# 7seg_interface_unit.net
KiCad netlist of a schematic drawn in EAGLE
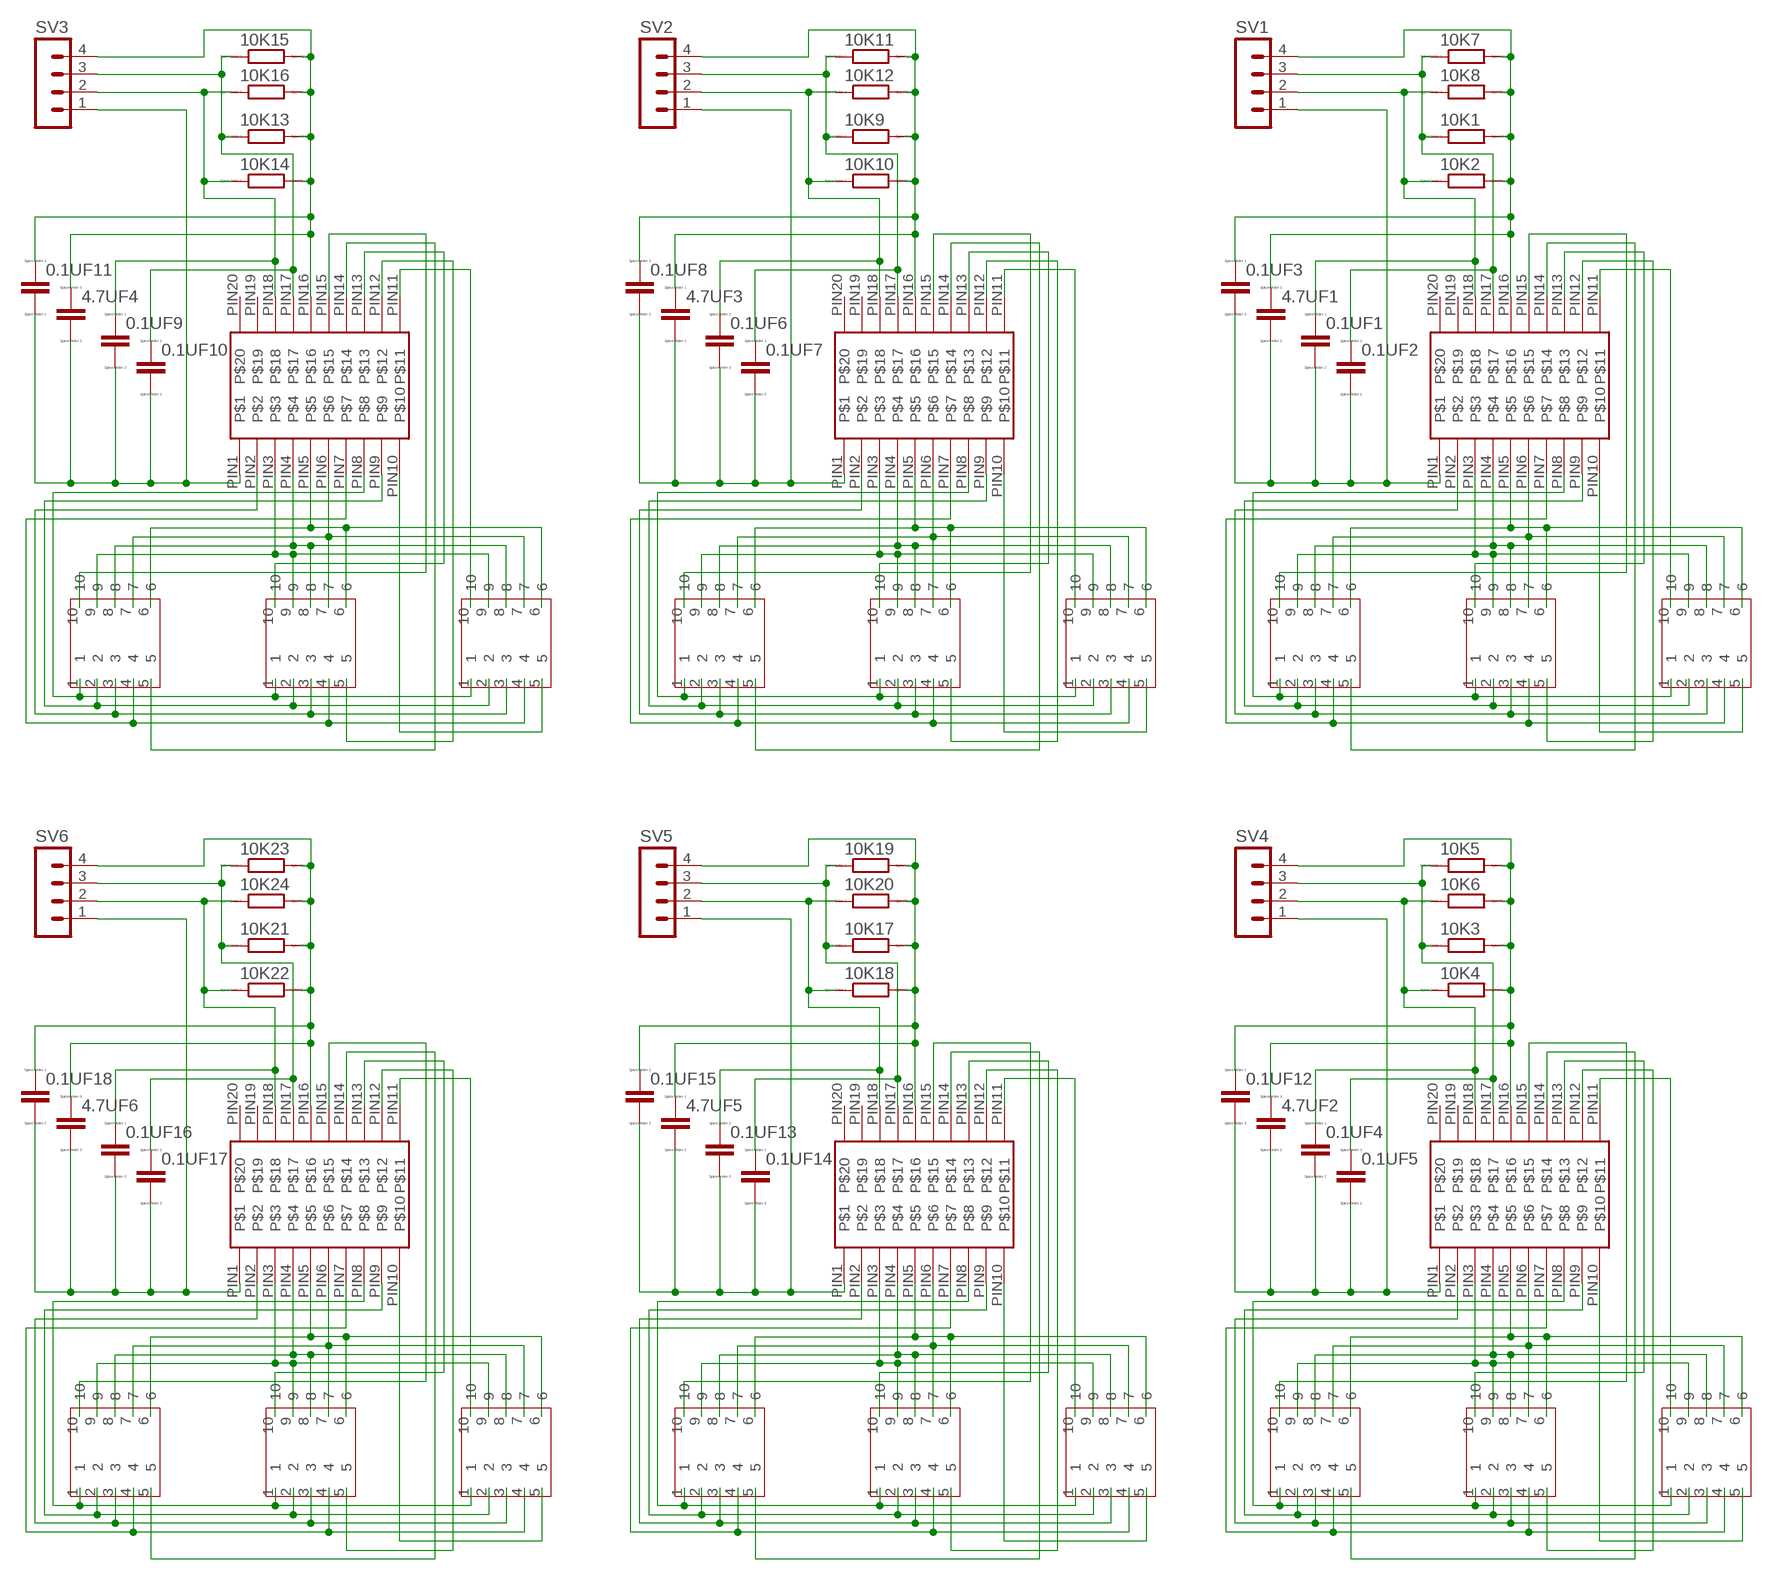
[diagram p0: schematic, sheet 1]

(export (version "E")
  (design (tool "Eeschema 10.0.6"))
  (components
    (comp (ref "0.1UF1")
      (value "CC1206")
      (footprint "eagle-import:C1206")
      (libsource (lib "eagle-import") (part "CC1206"))
    )
    (comp (ref "0.1UF2")
      (value "CC1206")
      (footprint "eagle-import:C1206")
      (libsource (lib "eagle-import") (part "CC1206"))
    )
    (comp (ref "0.1UF3")
      (value "CC1206")
      (footprint "eagle-import:C1206")
      (libsource (lib "eagle-import") (part "CC1206"))
    )
    (comp (ref "0.1UF4")
      (value "CC1206")
      (footprint "eagle-import:C1206")
      (libsource (lib "eagle-import") (part "CC1206"))
    )
    (comp (ref "0.1UF5")
      (value "CC1206")
      (footprint "eagle-import:C1206")
      (libsource (lib "eagle-import") (part "CC1206"))
    )
    (comp (ref "0.1UF6")
      (value "CC1206")
      (footprint "eagle-import:C1206")
      (libsource (lib "eagle-import") (part "CC1206"))
    )
    (comp (ref "0.1UF7")
      (value "CC1206")
      (footprint "eagle-import:C1206")
      (libsource (lib "eagle-import") (part "CC1206"))
    )
    (comp (ref "0.1UF8")
      (value "CC1206")
      (footprint "eagle-import:C1206")
      (libsource (lib "eagle-import") (part "CC1206"))
    )
    (comp (ref "0.1UF9")
      (value "CC1206")
      (footprint "eagle-import:C1206")
      (libsource (lib "eagle-import") (part "CC1206"))
    )
    (comp (ref "0.1UF10")
      (value "CC1206")
      (footprint "eagle-import:C1206")
      (libsource (lib "eagle-import") (part "CC1206"))
    )
    (comp (ref "0.1UF11")
      (value "CC1206")
      (footprint "eagle-import:C1206")
      (libsource (lib "eagle-import") (part "CC1206"))
    )
    (comp (ref "0.1UF12")
      (value "CC1206")
      (footprint "eagle-import:C1206")
      (libsource (lib "eagle-import") (part "CC1206"))
    )
    (comp (ref "0.1UF13")
      (value "CC1206")
      (footprint "eagle-import:C1206")
      (libsource (lib "eagle-import") (part "CC1206"))
    )
    (comp (ref "0.1UF14")
      (value "CC1206")
      (footprint "eagle-import:C1206")
      (libsource (lib "eagle-import") (part "CC1206"))
    )
    (comp (ref "0.1UF15")
      (value "CC1206")
      (footprint "eagle-import:C1206")
      (libsource (lib "eagle-import") (part "CC1206"))
    )
    (comp (ref "0.1UF16")
      (value "CC1206")
      (footprint "eagle-import:C1206")
      (libsource (lib "eagle-import") (part "CC1206"))
    )
    (comp (ref "0.1UF17")
      (value "CC1206")
      (footprint "eagle-import:C1206")
      (libsource (lib "eagle-import") (part "CC1206"))
    )
    (comp (ref "0.1UF18")
      (value "CC1206")
      (footprint "eagle-import:C1206")
      (libsource (lib "eagle-import") (part "CC1206"))
    )
    (comp (ref "4.7UF1")
      (value "CC2012")
      (footprint "eagle-import:C2012")
      (libsource (lib "eagle-import") (part "CC2012"))
    )
    (comp (ref "4.7UF2")
      (value "CC2012")
      (footprint "eagle-import:C2012")
      (libsource (lib "eagle-import") (part "CC2012"))
    )
    (comp (ref "4.7UF3")
      (value "CC2012")
      (footprint "eagle-import:C2012")
      (libsource (lib "eagle-import") (part "CC2012"))
    )
    (comp (ref "4.7UF4")
      (value "CC2012")
      (footprint "eagle-import:C2012")
      (libsource (lib "eagle-import") (part "CC2012"))
    )
    (comp (ref "4.7UF5")
      (value "CC2012")
      (footprint "eagle-import:C2012")
      (libsource (lib "eagle-import") (part "CC2012"))
    )
    (comp (ref "4.7UF6")
      (value "CC2012")
      (footprint "eagle-import:C2012")
      (libsource (lib "eagle-import") (part "CC2012"))
    )
    (comp (ref "10K1")
      (value "RR1206")
      (footprint "eagle-import:R1206")
      (libsource (lib "eagle-import") (part "RR1206"))
    )
    (comp (ref "10K2")
      (value "RR1206")
      (footprint "eagle-import:R1206")
      (libsource (lib "eagle-import") (part "RR1206"))
    )
    (comp (ref "10K3")
      (value "RR1206")
      (footprint "eagle-import:R1206")
      (libsource (lib "eagle-import") (part "RR1206"))
    )
    (comp (ref "10K4")
      (value "RR1206")
      (footprint "eagle-import:R1206")
      (libsource (lib "eagle-import") (part "RR1206"))
    )
    (comp (ref "10K5")
      (value "RR1206")
      (footprint "eagle-import:R1206")
      (libsource (lib "eagle-import") (part "RR1206"))
    )
    (comp (ref "10K6")
      (value "RR1206")
      (footprint "eagle-import:R1206")
      (libsource (lib "eagle-import") (part "RR1206"))
    )
    (comp (ref "10K7")
      (value "RR1206")
      (footprint "eagle-import:R1206")
      (libsource (lib "eagle-import") (part "RR1206"))
    )
    (comp (ref "10K8")
      (value "RR1206")
      (footprint "eagle-import:R1206")
      (libsource (lib "eagle-import") (part "RR1206"))
    )
    (comp (ref "10K9")
      (value "RR1206")
      (footprint "eagle-import:R1206")
      (libsource (lib "eagle-import") (part "RR1206"))
    )
    (comp (ref "10K10")
      (value "RR1206")
      (footprint "eagle-import:R1206")
      (libsource (lib "eagle-import") (part "RR1206"))
    )
    (comp (ref "10K11")
      (value "RR1206")
      (footprint "eagle-import:R1206")
      (libsource (lib "eagle-import") (part "RR1206"))
    )
    (comp (ref "10K12")
      (value "RR1206")
      (footprint "eagle-import:R1206")
      (libsource (lib "eagle-import") (part "RR1206"))
    )
    (comp (ref "10K13")
      (value "RR1206")
      (footprint "eagle-import:R1206")
      (libsource (lib "eagle-import") (part "RR1206"))
    )
    (comp (ref "10K14")
      (value "RR1206")
      (footprint "eagle-import:R1206")
      (libsource (lib "eagle-import") (part "RR1206"))
    )
    (comp (ref "10K15")
      (value "RR1206")
      (footprint "eagle-import:R1206")
      (libsource (lib "eagle-import") (part "RR1206"))
    )
    (comp (ref "10K16")
      (value "RR1206")
      (footprint "eagle-import:R1206")
      (libsource (lib "eagle-import") (part "RR1206"))
    )
    (comp (ref "10K17")
      (value "RR1206")
      (footprint "eagle-import:R1206")
      (libsource (lib "eagle-import") (part "RR1206"))
    )
    (comp (ref "10K18")
      (value "RR1206")
      (footprint "eagle-import:R1206")
      (libsource (lib "eagle-import") (part "RR1206"))
    )
    (comp (ref "10K19")
      (value "RR1206")
      (footprint "eagle-import:R1206")
      (libsource (lib "eagle-import") (part "RR1206"))
    )
    (comp (ref "10K20")
      (value "RR1206")
      (footprint "eagle-import:R1206")
      (libsource (lib "eagle-import") (part "RR1206"))
    )
    (comp (ref "10K21")
      (value "RR1206")
      (footprint "eagle-import:R1206")
      (libsource (lib "eagle-import") (part "RR1206"))
    )
    (comp (ref "10K22")
      (value "RR1206")
      (footprint "eagle-import:R1206")
      (libsource (lib "eagle-import") (part "RR1206"))
    )
    (comp (ref "10K23")
      (value "RR1206")
      (footprint "eagle-import:R1206")
      (libsource (lib "eagle-import") (part "RR1206"))
    )
    (comp (ref "10K24")
      (value "RR1206")
      (footprint "eagle-import:R1206")
      (libsource (lib "eagle-import") (part "RR1206"))
    )
    (comp (ref "LED1")
      (value "7SEG")
      (footprint "eagle-import:7SEG")
      (libsource (lib "eagle-import") (part "7SEG"))
    )
    (comp (ref "LED2")
      (value "7SEG")
      (footprint "eagle-import:7SEG")
      (libsource (lib "eagle-import") (part "7SEG"))
    )
    (comp (ref "LED3")
      (value "7SEG")
      (footprint "eagle-import:7SEG")
      (libsource (lib "eagle-import") (part "7SEG"))
    )
    (comp (ref "LED4")
      (value "7SEG")
      (footprint "eagle-import:7SEG")
      (libsource (lib "eagle-import") (part "7SEG"))
    )
    (comp (ref "LED5")
      (value "7SEG")
      (footprint "eagle-import:7SEG")
      (libsource (lib "eagle-import") (part "7SEG"))
    )
    (comp (ref "LED6")
      (value "7SEG")
      (footprint "eagle-import:7SEG")
      (libsource (lib "eagle-import") (part "7SEG"))
    )
    (comp (ref "LED7")
      (value "7SEG")
      (footprint "eagle-import:7SEG")
      (libsource (lib "eagle-import") (part "7SEG"))
    )
    (comp (ref "LED8")
      (value "7SEG")
      (footprint "eagle-import:7SEG")
      (libsource (lib "eagle-import") (part "7SEG"))
    )
    (comp (ref "LED9")
      (value "7SEG")
      (footprint "eagle-import:7SEG")
      (libsource (lib "eagle-import") (part "7SEG"))
    )
    (comp (ref "LED10")
      (value "7SEG")
      (footprint "eagle-import:7SEG")
      (libsource (lib "eagle-import") (part "7SEG"))
    )
    (comp (ref "LED11")
      (value "7SEG")
      (footprint "eagle-import:7SEG")
      (libsource (lib "eagle-import") (part "7SEG"))
    )
    (comp (ref "LED12")
      (value "7SEG")
      (footprint "eagle-import:7SEG")
      (libsource (lib "eagle-import") (part "7SEG"))
    )
    (comp (ref "LED13")
      (value "7SEG")
      (footprint "eagle-import:7SEG")
      (libsource (lib "eagle-import") (part "7SEG"))
    )
    (comp (ref "LED14")
      (value "7SEG")
      (footprint "eagle-import:7SEG")
      (libsource (lib "eagle-import") (part "7SEG"))
    )
    (comp (ref "LED15")
      (value "7SEG")
      (footprint "eagle-import:7SEG")
      (libsource (lib "eagle-import") (part "7SEG"))
    )
    (comp (ref "LED16")
      (value "7SEG")
      (footprint "eagle-import:7SEG")
      (libsource (lib "eagle-import") (part "7SEG"))
    )
    (comp (ref "LED17")
      (value "7SEG")
      (footprint "eagle-import:7SEG")
      (libsource (lib "eagle-import") (part "7SEG"))
    )
    (comp (ref "LED18")
      (value "7SEG")
      (footprint "eagle-import:7SEG")
      (libsource (lib "eagle-import") (part "7SEG"))
    )
    (comp (ref "SV1")
      (value "MA04-1")
      (footprint "eagle-import:MA04-1")
      (libsource (lib "eagle-import") (part "MA04-1"))
    )
    (comp (ref "SV2")
      (value "MA04-1")
      (footprint "eagle-import:MA04-1")
      (libsource (lib "eagle-import") (part "MA04-1"))
    )
    (comp (ref "SV3")
      (value "MA04-1")
      (footprint "eagle-import:MA04-1")
      (libsource (lib "eagle-import") (part "MA04-1"))
    )
    (comp (ref "SV4")
      (value "MA04-1")
      (footprint "eagle-import:MA04-1")
      (libsource (lib "eagle-import") (part "MA04-1"))
    )
    (comp (ref "SV5")
      (value "MA04-1")
      (footprint "eagle-import:MA04-1")
      (libsource (lib "eagle-import") (part "MA04-1"))
    )
    (comp (ref "SV6")
      (value "MA04-1")
      (footprint "eagle-import:MA04-1")
      (libsource (lib "eagle-import") (part "MA04-1"))
    )
    (comp (ref "TM1637-SMD1")
      (value "TM1637")
      (footprint "eagle-import:TM1637")
      (libsource (lib "eagle-import") (part "TM1637"))
    )
    (comp (ref "TM1637-SMD2")
      (value "TM1637")
      (footprint "eagle-import:TM1637")
      (libsource (lib "eagle-import") (part "TM1637"))
    )
    (comp (ref "TM1637-SMD3")
      (value "TM1637")
      (footprint "eagle-import:TM1637")
      (libsource (lib "eagle-import") (part "TM1637"))
    )
    (comp (ref "TM1637-SMD4")
      (value "TM1637")
      (footprint "eagle-import:TM1637")
      (libsource (lib "eagle-import") (part "TM1637"))
    )
    (comp (ref "TM1637-SMD5")
      (value "TM1637")
      (footprint "eagle-import:TM1637")
      (libsource (lib "eagle-import") (part "TM1637"))
    )
    (comp (ref "TM1637-SMD6")
      (value "TM1637")
      (footprint "eagle-import:TM1637")
      (libsource (lib "eagle-import") (part "TM1637"))
    )
  )
  (nets
    (net (code "1") (name "Net-(TM1637-SMD1-P$1)") (class "Default")
      (node (ref "0.1UF1") (pin "2") (pinfunction "2_2") (pintype "passive"))
      (node (ref "0.1UF2") (pin "2") (pinfunction "2_2") (pintype "passive"))
      (node (ref "0.1UF3") (pin "2") (pinfunction "2_2") (pintype "passive"))
      (node (ref "4.7UF1") (pin "2") (pinfunction "2_2") (pintype "passive"))
      (node (ref "SV1") (pin "1") (pinfunction "1_1") (pintype "passive"))
      (node (ref "TM1637-SMD1") (pin "PIN1") (pinfunction "P$1_PIN1") (pintype "bidirectional"))
    )
    (net (code "2") (name "Net-(TM1637-SMD1-P$2)") (class "Default")
      (node (ref "LED1") (pin "3") (pinfunction "3_3") (pintype "bidirectional"))
      (node (ref "LED2") (pin "3") (pinfunction "3_3") (pintype "bidirectional"))
      (node (ref "LED3") (pin "3") (pinfunction "3_3") (pintype "bidirectional"))
      (node (ref "TM1637-SMD1") (pin "PIN2") (pinfunction "P$2_PIN2") (pintype "bidirectional"))
    )
    (net (code "3") (name "Net-(TM1637-SMD1-P$3)") (class "Default")
      (node (ref "LED1") (pin "9") (pinfunction "9_9") (pintype "bidirectional"))
      (node (ref "LED2") (pin "9") (pinfunction "9_9") (pintype "bidirectional"))
      (node (ref "LED3") (pin "9") (pinfunction "9_9") (pintype "bidirectional"))
      (node (ref "TM1637-SMD1") (pin "PIN3") (pinfunction "P$3_PIN3") (pintype "bidirectional"))
    )
    (net (code "4") (name "Net-(TM1637-SMD1-P$4)") (class "Default")
      (node (ref "LED1") (pin "8") (pinfunction "8_8") (pintype "bidirectional"))
      (node (ref "LED2") (pin "8") (pinfunction "8_8") (pintype "bidirectional"))
      (node (ref "LED3") (pin "8") (pinfunction "8_8") (pintype "bidirectional"))
      (node (ref "TM1637-SMD1") (pin "PIN4") (pinfunction "P$4_PIN4") (pintype "bidirectional"))
    )
    (net (code "5") (name "Net-(TM1637-SMD1-P$5)") (class "Default")
      (node (ref "LED1") (pin "6") (pinfunction "6_6") (pintype "bidirectional"))
      (node (ref "LED2") (pin "6") (pinfunction "6_6") (pintype "bidirectional"))
      (node (ref "LED3") (pin "6") (pinfunction "6_6") (pintype "bidirectional"))
      (node (ref "TM1637-SMD1") (pin "PIN5") (pinfunction "P$5_PIN5") (pintype "bidirectional"))
    )
    (net (code "6") (name "Net-(TM1637-SMD1-P$6)") (class "Default")
      (node (ref "LED1") (pin "7") (pinfunction "7_7") (pintype "bidirectional"))
      (node (ref "LED2") (pin "7") (pinfunction "7_7") (pintype "bidirectional"))
      (node (ref "LED3") (pin "7") (pinfunction "7_7") (pintype "bidirectional"))
      (node (ref "TM1637-SMD1") (pin "PIN6") (pinfunction "P$6_PIN6") (pintype "bidirectional"))
    )
    (net (code "7") (name "Net-(TM1637-SMD1-P$7)") (class "Default")
      (node (ref "LED1") (pin "4") (pinfunction "4_4") (pintype "bidirectional"))
      (node (ref "LED2") (pin "4") (pinfunction "4_4") (pintype "bidirectional"))
      (node (ref "LED3") (pin "4") (pinfunction "4_4") (pintype "bidirectional"))
      (node (ref "TM1637-SMD1") (pin "PIN7") (pinfunction "P$7_PIN7") (pintype "bidirectional"))
    )
    (net (code "8") (name "Net-(TM1637-SMD1-P$8)") (class "Default")
      (node (ref "LED1") (pin "1") (pinfunction "1_1") (pintype "bidirectional"))
      (node (ref "LED2") (pin "1") (pinfunction "1_1") (pintype "bidirectional"))
      (node (ref "LED3") (pin "1") (pinfunction "1_1") (pintype "bidirectional"))
      (node (ref "TM1637-SMD1") (pin "PIN8") (pinfunction "P$8_PIN8") (pintype "bidirectional"))
    )
    (net (code "9") (name "Net-(TM1637-SMD1-P$9)") (class "Default")
      (node (ref "LED1") (pin "2") (pinfunction "2_2") (pintype "bidirectional"))
      (node (ref "LED2") (pin "2") (pinfunction "2_2") (pintype "bidirectional"))
      (node (ref "LED3") (pin "2") (pinfunction "2_2") (pintype "bidirectional"))
      (node (ref "TM1637-SMD1") (pin "PIN9") (pinfunction "P$9_PIN9") (pintype "bidirectional"))
    )
    (net (code "10") (name "Net-(TM1637-SMD1-P$10)") (class "Default")
      (node (ref "LED3") (pin "5") (pinfunction "5_5") (pintype "bidirectional"))
      (node (ref "TM1637-SMD1") (pin "PIN10") (pinfunction "P$10_PIN10") (pintype "bidirectional"))
    )
    (net (code "11") (name "Net-(TM1637-SMD1-P$11)") (class "Default")
      (node (ref "LED3") (pin "10") (pinfunction "10_10") (pintype "bidirectional"))
      (node (ref "TM1637-SMD1") (pin "PIN11") (pinfunction "P$11_PIN11") (pintype "bidirectional"))
    )
    (net (code "12") (name "Net-(TM1637-SMD1-P$12)") (class "Default")
      (node (ref "LED2") (pin "5") (pinfunction "5_5") (pintype "bidirectional"))
      (node (ref "TM1637-SMD1") (pin "PIN12") (pinfunction "P$12_PIN12") (pintype "bidirectional"))
    )
    (net (code "13") (name "Net-(TM1637-SMD1-P$13)") (class "Default")
      (node (ref "LED2") (pin "10") (pinfunction "10_10") (pintype "bidirectional"))
      (node (ref "TM1637-SMD1") (pin "PIN13") (pinfunction "P$13_PIN13") (pintype "bidirectional"))
    )
    (net (code "14") (name "Net-(TM1637-SMD1-P$14)") (class "Default")
      (node (ref "LED1") (pin "5") (pinfunction "5_5") (pintype "bidirectional"))
      (node (ref "TM1637-SMD1") (pin "PIN14") (pinfunction "P$14_PIN14") (pintype "bidirectional"))
    )
    (net (code "15") (name "Net-(TM1637-SMD1-P$15)") (class "Default")
      (node (ref "LED1") (pin "10") (pinfunction "10_10") (pintype "bidirectional"))
      (node (ref "TM1637-SMD1") (pin "PIN15") (pinfunction "P$15_PIN15") (pintype "bidirectional"))
    )
    (net (code "16") (name "Net-(TM1637-SMD1-P$16)") (class "Default")
      (node (ref "0.1UF3") (pin "1") (pinfunction "1_1") (pintype "passive"))
      (node (ref "10K1") (pin "2") (pinfunction "2_2") (pintype "passive"))
      (node (ref "10K2") (pin "2") (pinfunction "2_2") (pintype "passive"))
      (node (ref "10K7") (pin "2") (pinfunction "2_2") (pintype "passive"))
      (node (ref "10K8") (pin "2") (pinfunction "2_2") (pintype "passive"))
      (node (ref "4.7UF1") (pin "1") (pinfunction "1_1") (pintype "passive"))
      (node (ref "SV1") (pin "4") (pinfunction "4_4") (pintype "passive"))
      (node (ref "TM1637-SMD1") (pin "PIN16") (pinfunction "P$16_PIN16") (pintype "bidirectional"))
    )
    (net (code "17") (name "Net-(TM1637-SMD1-P$17)") (class "Default")
      (node (ref "0.1UF2") (pin "1") (pinfunction "1_1") (pintype "passive"))
      (node (ref "10K1") (pin "1") (pinfunction "1_1") (pintype "passive"))
      (node (ref "10K7") (pin "1") (pinfunction "1_1") (pintype "passive"))
      (node (ref "SV1") (pin "3") (pinfunction "3_3") (pintype "passive"))
      (node (ref "TM1637-SMD1") (pin "PIN17") (pinfunction "P$17_PIN17") (pintype "bidirectional"))
    )
    (net (code "18") (name "Net-(TM1637-SMD1-P$18)") (class "Default")
      (node (ref "0.1UF1") (pin "1") (pinfunction "1_1") (pintype "passive"))
      (node (ref "10K2") (pin "1") (pinfunction "1_1") (pintype "passive"))
      (node (ref "10K8") (pin "1") (pinfunction "1_1") (pintype "passive"))
      (node (ref "SV1") (pin "2") (pinfunction "2_2") (pintype "passive"))
      (node (ref "TM1637-SMD1") (pin "PIN18") (pinfunction "P$18_PIN18") (pintype "bidirectional"))
    )
    (net (code "19") (name "Net-(TM1637-SMD2-P$1)") (class "Default")
      (node (ref "0.1UF6") (pin "2") (pinfunction "2_2") (pintype "passive"))
      (node (ref "0.1UF7") (pin "2") (pinfunction "2_2") (pintype "passive"))
      (node (ref "0.1UF8") (pin "2") (pinfunction "2_2") (pintype "passive"))
      (node (ref "4.7UF3") (pin "2") (pinfunction "2_2") (pintype "passive"))
      (node (ref "SV2") (pin "1") (pinfunction "1_1") (pintype "passive"))
      (node (ref "TM1637-SMD2") (pin "PIN1") (pinfunction "P$1_PIN1") (pintype "bidirectional"))
    )
    (net (code "20") (name "Net-(TM1637-SMD2-P$2)") (class "Default")
      (node (ref "LED4") (pin "3") (pinfunction "3_3") (pintype "bidirectional"))
      (node (ref "LED5") (pin "3") (pinfunction "3_3") (pintype "bidirectional"))
      (node (ref "LED6") (pin "3") (pinfunction "3_3") (pintype "bidirectional"))
      (node (ref "TM1637-SMD2") (pin "PIN2") (pinfunction "P$2_PIN2") (pintype "bidirectional"))
    )
    (net (code "21") (name "Net-(TM1637-SMD2-P$3)") (class "Default")
      (node (ref "LED4") (pin "9") (pinfunction "9_9") (pintype "bidirectional"))
      (node (ref "LED5") (pin "9") (pinfunction "9_9") (pintype "bidirectional"))
      (node (ref "LED6") (pin "9") (pinfunction "9_9") (pintype "bidirectional"))
      (node (ref "TM1637-SMD2") (pin "PIN3") (pinfunction "P$3_PIN3") (pintype "bidirectional"))
    )
    (net (code "22") (name "Net-(TM1637-SMD2-P$4)") (class "Default")
      (node (ref "LED4") (pin "8") (pinfunction "8_8") (pintype "bidirectional"))
      (node (ref "LED5") (pin "8") (pinfunction "8_8") (pintype "bidirectional"))
      (node (ref "LED6") (pin "8") (pinfunction "8_8") (pintype "bidirectional"))
      (node (ref "TM1637-SMD2") (pin "PIN4") (pinfunction "P$4_PIN4") (pintype "bidirectional"))
    )
    (net (code "23") (name "Net-(TM1637-SMD2-P$5)") (class "Default")
      (node (ref "LED4") (pin "6") (pinfunction "6_6") (pintype "bidirectional"))
      (node (ref "LED5") (pin "6") (pinfunction "6_6") (pintype "bidirectional"))
      (node (ref "LED6") (pin "6") (pinfunction "6_6") (pintype "bidirectional"))
      (node (ref "TM1637-SMD2") (pin "PIN5") (pinfunction "P$5_PIN5") (pintype "bidirectional"))
    )
    (net (code "24") (name "Net-(TM1637-SMD2-P$6)") (class "Default")
      (node (ref "LED4") (pin "7") (pinfunction "7_7") (pintype "bidirectional"))
      (node (ref "LED5") (pin "7") (pinfunction "7_7") (pintype "bidirectional"))
      (node (ref "LED6") (pin "7") (pinfunction "7_7") (pintype "bidirectional"))
      (node (ref "TM1637-SMD2") (pin "PIN6") (pinfunction "P$6_PIN6") (pintype "bidirectional"))
    )
    (net (code "25") (name "Net-(TM1637-SMD2-P$7)") (class "Default")
      (node (ref "LED4") (pin "4") (pinfunction "4_4") (pintype "bidirectional"))
      (node (ref "LED5") (pin "4") (pinfunction "4_4") (pintype "bidirectional"))
      (node (ref "LED6") (pin "4") (pinfunction "4_4") (pintype "bidirectional"))
      (node (ref "TM1637-SMD2") (pin "PIN7") (pinfunction "P$7_PIN7") (pintype "bidirectional"))
    )
    (net (code "26") (name "Net-(TM1637-SMD2-P$8)") (class "Default")
      (node (ref "LED4") (pin "1") (pinfunction "1_1") (pintype "bidirectional"))
      (node (ref "LED5") (pin "1") (pinfunction "1_1") (pintype "bidirectional"))
      (node (ref "LED6") (pin "1") (pinfunction "1_1") (pintype "bidirectional"))
      (node (ref "TM1637-SMD2") (pin "PIN8") (pinfunction "P$8_PIN8") (pintype "bidirectional"))
    )
    (net (code "27") (name "Net-(TM1637-SMD2-P$9)") (class "Default")
      (node (ref "LED4") (pin "2") (pinfunction "2_2") (pintype "bidirectional"))
      (node (ref "LED5") (pin "2") (pinfunction "2_2") (pintype "bidirectional"))
      (node (ref "LED6") (pin "2") (pinfunction "2_2") (pintype "bidirectional"))
      (node (ref "TM1637-SMD2") (pin "PIN9") (pinfunction "P$9_PIN9") (pintype "bidirectional"))
    )
    (net (code "28") (name "Net-(TM1637-SMD2-P$10)") (class "Default")
      (node (ref "LED5") (pin "5") (pinfunction "5_5") (pintype "bidirectional"))
      (node (ref "TM1637-SMD2") (pin "PIN10") (pinfunction "P$10_PIN10") (pintype "bidirectional"))
    )
    (net (code "29") (name "Net-(TM1637-SMD2-P$11)") (class "Default")
      (node (ref "LED5") (pin "10") (pinfunction "10_10") (pintype "bidirectional"))
      (node (ref "TM1637-SMD2") (pin "PIN11") (pinfunction "P$11_PIN11") (pintype "bidirectional"))
    )
    (net (code "30") (name "Net-(TM1637-SMD2-P$12)") (class "Default")
      (node (ref "LED4") (pin "5") (pinfunction "5_5") (pintype "bidirectional"))
      (node (ref "TM1637-SMD2") (pin "PIN12") (pinfunction "P$12_PIN12") (pintype "bidirectional"))
    )
    (net (code "31") (name "Net-(TM1637-SMD2-P$13)") (class "Default")
      (node (ref "LED4") (pin "10") (pinfunction "10_10") (pintype "bidirectional"))
      (node (ref "TM1637-SMD2") (pin "PIN13") (pinfunction "P$13_PIN13") (pintype "bidirectional"))
    )
    (net (code "32") (name "Net-(TM1637-SMD2-P$14)") (class "Default")
      (node (ref "LED6") (pin "5") (pinfunction "5_5") (pintype "bidirectional"))
      (node (ref "TM1637-SMD2") (pin "PIN14") (pinfunction "P$14_PIN14") (pintype "bidirectional"))
    )
    (net (code "33") (name "Net-(TM1637-SMD2-P$15)") (class "Default")
      (node (ref "LED6") (pin "10") (pinfunction "10_10") (pintype "bidirectional"))
      (node (ref "TM1637-SMD2") (pin "PIN15") (pinfunction "P$15_PIN15") (pintype "bidirectional"))
    )
    (net (code "34") (name "Net-(TM1637-SMD2-P$16)") (class "Default")
      (node (ref "0.1UF8") (pin "1") (pinfunction "1_1") (pintype "passive"))
      (node (ref "10K10") (pin "2") (pinfunction "2_2") (pintype "passive"))
      (node (ref "10K11") (pin "2") (pinfunction "2_2") (pintype "passive"))
      (node (ref "10K12") (pin "2") (pinfunction "2_2") (pintype "passive"))
      (node (ref "10K9") (pin "2") (pinfunction "2_2") (pintype "passive"))
      (node (ref "4.7UF3") (pin "1") (pinfunction "1_1") (pintype "passive"))
      (node (ref "SV2") (pin "4") (pinfunction "4_4") (pintype "passive"))
      (node (ref "TM1637-SMD2") (pin "PIN16") (pinfunction "P$16_PIN16") (pintype "bidirectional"))
    )
    (net (code "35") (name "Net-(TM1637-SMD2-P$17)") (class "Default")
      (node (ref "0.1UF7") (pin "1") (pinfunction "1_1") (pintype "passive"))
      (node (ref "10K11") (pin "1") (pinfunction "1_1") (pintype "passive"))
      (node (ref "10K9") (pin "1") (pinfunction "1_1") (pintype "passive"))
      (node (ref "SV2") (pin "3") (pinfunction "3_3") (pintype "passive"))
      (node (ref "TM1637-SMD2") (pin "PIN17") (pinfunction "P$17_PIN17") (pintype "bidirectional"))
    )
    (net (code "36") (name "Net-(TM1637-SMD2-P$18)") (class "Default")
      (node (ref "0.1UF6") (pin "1") (pinfunction "1_1") (pintype "passive"))
      (node (ref "10K10") (pin "1") (pinfunction "1_1") (pintype "passive"))
      (node (ref "10K12") (pin "1") (pinfunction "1_1") (pintype "passive"))
      (node (ref "SV2") (pin "2") (pinfunction "2_2") (pintype "passive"))
      (node (ref "TM1637-SMD2") (pin "PIN18") (pinfunction "P$18_PIN18") (pintype "bidirectional"))
    )
    (net (code "37") (name "Net-(TM1637-SMD3-P$1)") (class "Default")
      (node (ref "0.1UF10") (pin "2") (pinfunction "2_2") (pintype "passive"))
      (node (ref "0.1UF11") (pin "2") (pinfunction "2_2") (pintype "passive"))
      (node (ref "0.1UF9") (pin "2") (pinfunction "2_2") (pintype "passive"))
      (node (ref "4.7UF4") (pin "2") (pinfunction "2_2") (pintype "passive"))
      (node (ref "SV3") (pin "1") (pinfunction "1_1") (pintype "passive"))
      (node (ref "TM1637-SMD3") (pin "PIN1") (pinfunction "P$1_PIN1") (pintype "bidirectional"))
    )
    (net (code "38") (name "Net-(TM1637-SMD3-P$2)") (class "Default")
      (node (ref "LED7") (pin "3") (pinfunction "3_3") (pintype "bidirectional"))
      (node (ref "LED8") (pin "3") (pinfunction "3_3") (pintype "bidirectional"))
      (node (ref "LED9") (pin "3") (pinfunction "3_3") (pintype "bidirectional"))
      (node (ref "TM1637-SMD3") (pin "PIN2") (pinfunction "P$2_PIN2") (pintype "bidirectional"))
    )
    (net (code "39") (name "Net-(TM1637-SMD3-P$3)") (class "Default")
      (node (ref "LED7") (pin "9") (pinfunction "9_9") (pintype "bidirectional"))
      (node (ref "LED8") (pin "9") (pinfunction "9_9") (pintype "bidirectional"))
      (node (ref "LED9") (pin "9") (pinfunction "9_9") (pintype "bidirectional"))
      (node (ref "TM1637-SMD3") (pin "PIN3") (pinfunction "P$3_PIN3") (pintype "bidirectional"))
    )
    (net (code "40") (name "Net-(TM1637-SMD3-P$4)") (class "Default")
      (node (ref "LED7") (pin "8") (pinfunction "8_8") (pintype "bidirectional"))
      (node (ref "LED8") (pin "8") (pinfunction "8_8") (pintype "bidirectional"))
      (node (ref "LED9") (pin "8") (pinfunction "8_8") (pintype "bidirectional"))
      (node (ref "TM1637-SMD3") (pin "PIN4") (pinfunction "P$4_PIN4") (pintype "bidirectional"))
    )
    (net (code "41") (name "Net-(TM1637-SMD3-P$5)") (class "Default")
      (node (ref "LED7") (pin "6") (pinfunction "6_6") (pintype "bidirectional"))
      (node (ref "LED8") (pin "6") (pinfunction "6_6") (pintype "bidirectional"))
      (node (ref "LED9") (pin "6") (pinfunction "6_6") (pintype "bidirectional"))
      (node (ref "TM1637-SMD3") (pin "PIN5") (pinfunction "P$5_PIN5") (pintype "bidirectional"))
    )
    (net (code "42") (name "Net-(TM1637-SMD3-P$6)") (class "Default")
      (node (ref "LED7") (pin "7") (pinfunction "7_7") (pintype "bidirectional"))
      (node (ref "LED8") (pin "7") (pinfunction "7_7") (pintype "bidirectional"))
      (node (ref "LED9") (pin "7") (pinfunction "7_7") (pintype "bidirectional"))
      (node (ref "TM1637-SMD3") (pin "PIN6") (pinfunction "P$6_PIN6") (pintype "bidirectional"))
    )
    (net (code "43") (name "Net-(TM1637-SMD3-P$7)") (class "Default")
      (node (ref "LED7") (pin "4") (pinfunction "4_4") (pintype "bidirectional"))
      (node (ref "LED8") (pin "4") (pinfunction "4_4") (pintype "bidirectional"))
      (node (ref "LED9") (pin "4") (pinfunction "4_4") (pintype "bidirectional"))
      (node (ref "TM1637-SMD3") (pin "PIN7") (pinfunction "P$7_PIN7") (pintype "bidirectional"))
    )
    (net (code "44") (name "Net-(TM1637-SMD3-P$8)") (class "Default")
      (node (ref "LED7") (pin "1") (pinfunction "1_1") (pintype "bidirectional"))
      (node (ref "LED8") (pin "1") (pinfunction "1_1") (pintype "bidirectional"))
      (node (ref "LED9") (pin "1") (pinfunction "1_1") (pintype "bidirectional"))
      (node (ref "TM1637-SMD3") (pin "PIN8") (pinfunction "P$8_PIN8") (pintype "bidirectional"))
    )
    (net (code "45") (name "Net-(TM1637-SMD3-P$9)") (class "Default")
      (node (ref "LED7") (pin "2") (pinfunction "2_2") (pintype "bidirectional"))
      (node (ref "LED8") (pin "2") (pinfunction "2_2") (pintype "bidirectional"))
      (node (ref "LED9") (pin "2") (pinfunction "2_2") (pintype "bidirectional"))
      (node (ref "TM1637-SMD3") (pin "PIN9") (pinfunction "P$9_PIN9") (pintype "bidirectional"))
    )
    (net (code "46") (name "Net-(TM1637-SMD3-P$10)") (class "Default")
      (node (ref "LED8") (pin "5") (pinfunction "5_5") (pintype "bidirectional"))
      (node (ref "TM1637-SMD3") (pin "PIN10") (pinfunction "P$10_PIN10") (pintype "bidirectional"))
    )
    (net (code "47") (name "Net-(TM1637-SMD3-P$11)") (class "Default")
      (node (ref "LED8") (pin "10") (pinfunction "10_10") (pintype "bidirectional"))
      (node (ref "TM1637-SMD3") (pin "PIN11") (pinfunction "P$11_PIN11") (pintype "bidirectional"))
    )
    (net (code "48") (name "Net-(TM1637-SMD3-P$12)") (class "Default")
      (node (ref "LED7") (pin "5") (pinfunction "5_5") (pintype "bidirectional"))
      (node (ref "TM1637-SMD3") (pin "PIN12") (pinfunction "P$12_PIN12") (pintype "bidirectional"))
    )
    (net (code "49") (name "Net-(TM1637-SMD3-P$13)") (class "Default")
      (node (ref "LED7") (pin "10") (pinfunction "10_10") (pintype "bidirectional"))
      (node (ref "TM1637-SMD3") (pin "PIN13") (pinfunction "P$13_PIN13") (pintype "bidirectional"))
    )
    (net (code "50") (name "Net-(TM1637-SMD3-P$14)") (class "Default")
      (node (ref "LED9") (pin "5") (pinfunction "5_5") (pintype "bidirectional"))
      (node (ref "TM1637-SMD3") (pin "PIN14") (pinfunction "P$14_PIN14") (pintype "bidirectional"))
    )
    (net (code "51") (name "Net-(TM1637-SMD3-P$15)") (class "Default")
      (node (ref "LED9") (pin "10") (pinfunction "10_10") (pintype "bidirectional"))
      (node (ref "TM1637-SMD3") (pin "PIN15") (pinfunction "P$15_PIN15") (pintype "bidirectional"))
    )
    (net (code "52") (name "Net-(TM1637-SMD3-P$16)") (class "Default")
      (node (ref "0.1UF11") (pin "1") (pinfunction "1_1") (pintype "passive"))
      (node (ref "10K13") (pin "2") (pinfunction "2_2") (pintype "passive"))
      (node (ref "10K14") (pin "2") (pinfunction "2_2") (pintype "passive"))
      (node (ref "10K15") (pin "2") (pinfunction "2_2") (pintype "passive"))
      (node (ref "10K16") (pin "2") (pinfunction "2_2") (pintype "passive"))
      (node (ref "4.7UF4") (pin "1") (pinfunction "1_1") (pintype "passive"))
      (node (ref "SV3") (pin "4") (pinfunction "4_4") (pintype "passive"))
      (node (ref "TM1637-SMD3") (pin "PIN16") (pinfunction "P$16_PIN16") (pintype "bidirectional"))
    )
    (net (code "53") (name "Net-(TM1637-SMD3-P$17)") (class "Default")
      (node (ref "0.1UF10") (pin "1") (pinfunction "1_1") (pintype "passive"))
      (node (ref "10K13") (pin "1") (pinfunction "1_1") (pintype "passive"))
      (node (ref "10K15") (pin "1") (pinfunction "1_1") (pintype "passive"))
      (node (ref "SV3") (pin "3") (pinfunction "3_3") (pintype "passive"))
      (node (ref "TM1637-SMD3") (pin "PIN17") (pinfunction "P$17_PIN17") (pintype "bidirectional"))
    )
    (net (code "54") (name "Net-(TM1637-SMD3-P$18)") (class "Default")
      (node (ref "0.1UF9") (pin "1") (pinfunction "1_1") (pintype "passive"))
      (node (ref "10K14") (pin "1") (pinfunction "1_1") (pintype "passive"))
      (node (ref "10K16") (pin "1") (pinfunction "1_1") (pintype "passive"))
      (node (ref "SV3") (pin "2") (pinfunction "2_2") (pintype "passive"))
      (node (ref "TM1637-SMD3") (pin "PIN18") (pinfunction "P$18_PIN18") (pintype "bidirectional"))
    )
    (net (code "55") (name "Net-(TM1637-SMD4-P$1)") (class "Default")
      (node (ref "0.1UF12") (pin "2") (pinfunction "2_2") (pintype "passive"))
      (node (ref "0.1UF4") (pin "2") (pinfunction "2_2") (pintype "passive"))
      (node (ref "0.1UF5") (pin "2") (pinfunction "2_2") (pintype "passive"))
      (node (ref "4.7UF2") (pin "2") (pinfunction "2_2") (pintype "passive"))
      (node (ref "SV4") (pin "1") (pinfunction "1_1") (pintype "passive"))
      (node (ref "TM1637-SMD4") (pin "PIN1") (pinfunction "P$1_PIN1") (pintype "bidirectional"))
    )
    (net (code "56") (name "Net-(TM1637-SMD4-P$2)") (class "Default")
      (node (ref "LED10") (pin "3") (pinfunction "3_3") (pintype "bidirectional"))
      (node (ref "LED11") (pin "3") (pinfunction "3_3") (pintype "bidirectional"))
      (node (ref "LED12") (pin "3") (pinfunction "3_3") (pintype "bidirectional"))
      (node (ref "TM1637-SMD4") (pin "PIN2") (pinfunction "P$2_PIN2") (pintype "bidirectional"))
    )
    (net (code "57") (name "Net-(TM1637-SMD4-P$3)") (class "Default")
      (node (ref "LED10") (pin "9") (pinfunction "9_9") (pintype "bidirectional"))
      (node (ref "LED11") (pin "9") (pinfunction "9_9") (pintype "bidirectional"))
      (node (ref "LED12") (pin "9") (pinfunction "9_9") (pintype "bidirectional"))
      (node (ref "TM1637-SMD4") (pin "PIN3") (pinfunction "P$3_PIN3") (pintype "bidirectional"))
    )
    (net (code "58") (name "Net-(TM1637-SMD4-P$4)") (class "Default")
      (node (ref "LED10") (pin "8") (pinfunction "8_8") (pintype "bidirectional"))
      (node (ref "LED11") (pin "8") (pinfunction "8_8") (pintype "bidirectional"))
      (node (ref "LED12") (pin "8") (pinfunction "8_8") (pintype "bidirectional"))
      (node (ref "TM1637-SMD4") (pin "PIN4") (pinfunction "P$4_PIN4") (pintype "bidirectional"))
    )
    (net (code "59") (name "Net-(TM1637-SMD4-P$5)") (class "Default")
      (node (ref "LED10") (pin "6") (pinfunction "6_6") (pintype "bidirectional"))
      (node (ref "LED11") (pin "6") (pinfunction "6_6") (pintype "bidirectional"))
      (node (ref "LED12") (pin "6") (pinfunction "6_6") (pintype "bidirectional"))
      (node (ref "TM1637-SMD4") (pin "PIN5") (pinfunction "P$5_PIN5") (pintype "bidirectional"))
    )
    (net (code "60") (name "Net-(TM1637-SMD4-P$6)") (class "Default")
      (node (ref "LED10") (pin "7") (pinfunction "7_7") (pintype "bidirectional"))
      (node (ref "LED11") (pin "7") (pinfunction "7_7") (pintype "bidirectional"))
      (node (ref "LED12") (pin "7") (pinfunction "7_7") (pintype "bidirectional"))
      (node (ref "TM1637-SMD4") (pin "PIN6") (pinfunction "P$6_PIN6") (pintype "bidirectional"))
    )
    (net (code "61") (name "Net-(TM1637-SMD4-P$7)") (class "Default")
      (node (ref "LED10") (pin "4") (pinfunction "4_4") (pintype "bidirectional"))
      (node (ref "LED11") (pin "4") (pinfunction "4_4") (pintype "bidirectional"))
      (node (ref "LED12") (pin "4") (pinfunction "4_4") (pintype "bidirectional"))
      (node (ref "TM1637-SMD4") (pin "PIN7") (pinfunction "P$7_PIN7") (pintype "bidirectional"))
    )
    (net (code "62") (name "Net-(TM1637-SMD4-P$8)") (class "Default")
      (node (ref "LED10") (pin "1") (pinfunction "1_1") (pintype "bidirectional"))
      (node (ref "LED11") (pin "1") (pinfunction "1_1") (pintype "bidirectional"))
      (node (ref "LED12") (pin "1") (pinfunction "1_1") (pintype "bidirectional"))
      (node (ref "TM1637-SMD4") (pin "PIN8") (pinfunction "P$8_PIN8") (pintype "bidirectional"))
    )
    (net (code "63") (name "Net-(TM1637-SMD4-P$9)") (class "Default")
      (node (ref "LED10") (pin "2") (pinfunction "2_2") (pintype "bidirectional"))
      (node (ref "LED11") (pin "2") (pinfunction "2_2") (pintype "bidirectional"))
      (node (ref "LED12") (pin "2") (pinfunction "2_2") (pintype "bidirectional"))
      (node (ref "TM1637-SMD4") (pin "PIN9") (pinfunction "P$9_PIN9") (pintype "bidirectional"))
    )
    (net (code "64") (name "Net-(TM1637-SMD4-P$10)") (class "Default")
      (node (ref "LED11") (pin "5") (pinfunction "5_5") (pintype "bidirectional"))
      (node (ref "TM1637-SMD4") (pin "PIN10") (pinfunction "P$10_PIN10") (pintype "bidirectional"))
    )
    (net (code "65") (name "Net-(TM1637-SMD4-P$11)") (class "Default")
      (node (ref "LED11") (pin "10") (pinfunction "10_10") (pintype "bidirectional"))
      (node (ref "TM1637-SMD4") (pin "PIN11") (pinfunction "P$11_PIN11") (pintype "bidirectional"))
    )
    (net (code "66") (name "Net-(TM1637-SMD4-P$12)") (class "Default")
      (node (ref "LED10") (pin "5") (pinfunction "5_5") (pintype "bidirectional"))
      (node (ref "TM1637-SMD4") (pin "PIN12") (pinfunction "P$12_PIN12") (pintype "bidirectional"))
    )
    (net (code "67") (name "Net-(TM1637-SMD4-P$13)") (class "Default")
      (node (ref "LED10") (pin "10") (pinfunction "10_10") (pintype "bidirectional"))
      (node (ref "TM1637-SMD4") (pin "PIN13") (pinfunction "P$13_PIN13") (pintype "bidirectional"))
    )
    (net (code "68") (name "Net-(TM1637-SMD4-P$14)") (class "Default")
      (node (ref "LED12") (pin "5") (pinfunction "5_5") (pintype "bidirectional"))
      (node (ref "TM1637-SMD4") (pin "PIN14") (pinfunction "P$14_PIN14") (pintype "bidirectional"))
    )
    (net (code "69") (name "Net-(TM1637-SMD4-P$15)") (class "Default")
      (node (ref "LED12") (pin "10") (pinfunction "10_10") (pintype "bidirectional"))
      (node (ref "TM1637-SMD4") (pin "PIN15") (pinfunction "P$15_PIN15") (pintype "bidirectional"))
    )
    (net (code "70") (name "Net-(TM1637-SMD4-P$16)") (class "Default")
      (node (ref "0.1UF12") (pin "1") (pinfunction "1_1") (pintype "passive"))
      (node (ref "10K3") (pin "2") (pinfunction "2_2") (pintype "passive"))
      (node (ref "10K4") (pin "2") (pinfunction "2_2") (pintype "passive"))
      (node (ref "10K5") (pin "2") (pinfunction "2_2") (pintype "passive"))
      (node (ref "10K6") (pin "2") (pinfunction "2_2") (pintype "passive"))
      (node (ref "4.7UF2") (pin "1") (pinfunction "1_1") (pintype "passive"))
      (node (ref "SV4") (pin "4") (pinfunction "4_4") (pintype "passive"))
      (node (ref "TM1637-SMD4") (pin "PIN16") (pinfunction "P$16_PIN16") (pintype "bidirectional"))
    )
    (net (code "71") (name "Net-(TM1637-SMD4-P$17)") (class "Default")
      (node (ref "0.1UF5") (pin "1") (pinfunction "1_1") (pintype "passive"))
      (node (ref "10K3") (pin "1") (pinfunction "1_1") (pintype "passive"))
      (node (ref "10K5") (pin "1") (pinfunction "1_1") (pintype "passive"))
      (node (ref "SV4") (pin "3") (pinfunction "3_3") (pintype "passive"))
      (node (ref "TM1637-SMD4") (pin "PIN17") (pinfunction "P$17_PIN17") (pintype "bidirectional"))
    )
    (net (code "72") (name "Net-(TM1637-SMD4-P$18)") (class "Default")
      (node (ref "0.1UF4") (pin "1") (pinfunction "1_1") (pintype "passive"))
      (node (ref "10K4") (pin "1") (pinfunction "1_1") (pintype "passive"))
      (node (ref "10K6") (pin "1") (pinfunction "1_1") (pintype "passive"))
      (node (ref "SV4") (pin "2") (pinfunction "2_2") (pintype "passive"))
      (node (ref "TM1637-SMD4") (pin "PIN18") (pinfunction "P$18_PIN18") (pintype "bidirectional"))
    )
    (net (code "73") (name "Net-(TM1637-SMD5-P$1)") (class "Default")
      (node (ref "0.1UF13") (pin "2") (pinfunction "2_2") (pintype "passive"))
      (node (ref "0.1UF14") (pin "2") (pinfunction "2_2") (pintype "passive"))
      (node (ref "0.1UF15") (pin "2") (pinfunction "2_2") (pintype "passive"))
      (node (ref "4.7UF5") (pin "2") (pinfunction "2_2") (pintype "passive"))
      (node (ref "SV5") (pin "1") (pinfunction "1_1") (pintype "passive"))
      (node (ref "TM1637-SMD5") (pin "PIN1") (pinfunction "P$1_PIN1") (pintype "bidirectional"))
    )
    (net (code "74") (name "Net-(TM1637-SMD5-P$2)") (class "Default")
      (node (ref "LED13") (pin "3") (pinfunction "3_3") (pintype "bidirectional"))
      (node (ref "LED14") (pin "3") (pinfunction "3_3") (pintype "bidirectional"))
      (node (ref "LED15") (pin "3") (pinfunction "3_3") (pintype "bidirectional"))
      (node (ref "TM1637-SMD5") (pin "PIN2") (pinfunction "P$2_PIN2") (pintype "bidirectional"))
    )
    (net (code "75") (name "Net-(TM1637-SMD5-P$3)") (class "Default")
      (node (ref "LED13") (pin "9") (pinfunction "9_9") (pintype "bidirectional"))
      (node (ref "LED14") (pin "9") (pinfunction "9_9") (pintype "bidirectional"))
      (node (ref "LED15") (pin "9") (pinfunction "9_9") (pintype "bidirectional"))
      (node (ref "TM1637-SMD5") (pin "PIN3") (pinfunction "P$3_PIN3") (pintype "bidirectional"))
    )
    (net (code "76") (name "Net-(TM1637-SMD5-P$4)") (class "Default")
      (node (ref "LED13") (pin "8") (pinfunction "8_8") (pintype "bidirectional"))
      (node (ref "LED14") (pin "8") (pinfunction "8_8") (pintype "bidirectional"))
      (node (ref "LED15") (pin "8") (pinfunction "8_8") (pintype "bidirectional"))
      (node (ref "TM1637-SMD5") (pin "PIN4") (pinfunction "P$4_PIN4") (pintype "bidirectional"))
    )
    (net (code "77") (name "Net-(TM1637-SMD5-P$5)") (class "Default")
      (node (ref "LED13") (pin "6") (pinfunction "6_6") (pintype "bidirectional"))
      (node (ref "LED14") (pin "6") (pinfunction "6_6") (pintype "bidirectional"))
      (node (ref "LED15") (pin "6") (pinfunction "6_6") (pintype "bidirectional"))
      (node (ref "TM1637-SMD5") (pin "PIN5") (pinfunction "P$5_PIN5") (pintype "bidirectional"))
    )
    (net (code "78") (name "Net-(TM1637-SMD5-P$6)") (class "Default")
      (node (ref "LED13") (pin "7") (pinfunction "7_7") (pintype "bidirectional"))
      (node (ref "LED14") (pin "7") (pinfunction "7_7") (pintype "bidirectional"))
      (node (ref "LED15") (pin "7") (pinfunction "7_7") (pintype "bidirectional"))
      (node (ref "TM1637-SMD5") (pin "PIN6") (pinfunction "P$6_PIN6") (pintype "bidirectional"))
    )
    (net (code "79") (name "Net-(TM1637-SMD5-P$7)") (class "Default")
      (node (ref "LED13") (pin "4") (pinfunction "4_4") (pintype "bidirectional"))
      (node (ref "LED14") (pin "4") (pinfunction "4_4") (pintype "bidirectional"))
      (node (ref "LED15") (pin "4") (pinfunction "4_4") (pintype "bidirectional"))
      (node (ref "TM1637-SMD5") (pin "PIN7") (pinfunction "P$7_PIN7") (pintype "bidirectional"))
    )
    (net (code "80") (name "Net-(TM1637-SMD5-P$8)") (class "Default")
      (node (ref "LED13") (pin "1") (pinfunction "1_1") (pintype "bidirectional"))
      (node (ref "LED14") (pin "1") (pinfunction "1_1") (pintype "bidirectional"))
      (node (ref "LED15") (pin "1") (pinfunction "1_1") (pintype "bidirectional"))
      (node (ref "TM1637-SMD5") (pin "PIN8") (pinfunction "P$8_PIN8") (pintype "bidirectional"))
    )
    (net (code "81") (name "Net-(TM1637-SMD5-P$9)") (class "Default")
      (node (ref "LED13") (pin "2") (pinfunction "2_2") (pintype "bidirectional"))
      (node (ref "LED14") (pin "2") (pinfunction "2_2") (pintype "bidirectional"))
      (node (ref "LED15") (pin "2") (pinfunction "2_2") (pintype "bidirectional"))
      (node (ref "TM1637-SMD5") (pin "PIN9") (pinfunction "P$9_PIN9") (pintype "bidirectional"))
    )
    (net (code "82") (name "Net-(TM1637-SMD5-P$10)") (class "Default")
      (node (ref "LED14") (pin "5") (pinfunction "5_5") (pintype "bidirectional"))
      (node (ref "TM1637-SMD5") (pin "PIN10") (pinfunction "P$10_PIN10") (pintype "bidirectional"))
    )
    (net (code "83") (name "Net-(TM1637-SMD5-P$11)") (class "Default")
      (node (ref "LED14") (pin "10") (pinfunction "10_10") (pintype "bidirectional"))
      (node (ref "TM1637-SMD5") (pin "PIN11") (pinfunction "P$11_PIN11") (pintype "bidirectional"))
    )
    (net (code "84") (name "Net-(TM1637-SMD5-P$12)") (class "Default")
      (node (ref "LED13") (pin "5") (pinfunction "5_5") (pintype "bidirectional"))
      (node (ref "TM1637-SMD5") (pin "PIN12") (pinfunction "P$12_PIN12") (pintype "bidirectional"))
    )
    (net (code "85") (name "Net-(TM1637-SMD5-P$13)") (class "Default")
      (node (ref "LED13") (pin "10") (pinfunction "10_10") (pintype "bidirectional"))
      (node (ref "TM1637-SMD5") (pin "PIN13") (pinfunction "P$13_PIN13") (pintype "bidirectional"))
    )
    (net (code "86") (name "Net-(TM1637-SMD5-P$14)") (class "Default")
      (node (ref "LED15") (pin "5") (pinfunction "5_5") (pintype "bidirectional"))
      (node (ref "TM1637-SMD5") (pin "PIN14") (pinfunction "P$14_PIN14") (pintype "bidirectional"))
    )
    (net (code "87") (name "Net-(TM1637-SMD5-P$15)") (class "Default")
      (node (ref "LED15") (pin "10") (pinfunction "10_10") (pintype "bidirectional"))
      (node (ref "TM1637-SMD5") (pin "PIN15") (pinfunction "P$15_PIN15") (pintype "bidirectional"))
    )
    (net (code "88") (name "Net-(TM1637-SMD5-P$16)") (class "Default")
      (node (ref "0.1UF15") (pin "1") (pinfunction "1_1") (pintype "passive"))
      (node (ref "10K17") (pin "2") (pinfunction "2_2") (pintype "passive"))
      (node (ref "10K18") (pin "2") (pinfunction "2_2") (pintype "passive"))
      (node (ref "10K19") (pin "2") (pinfunction "2_2") (pintype "passive"))
      (node (ref "10K20") (pin "2") (pinfunction "2_2") (pintype "passive"))
      (node (ref "4.7UF5") (pin "1") (pinfunction "1_1") (pintype "passive"))
      (node (ref "SV5") (pin "4") (pinfunction "4_4") (pintype "passive"))
      (node (ref "TM1637-SMD5") (pin "PIN16") (pinfunction "P$16_PIN16") (pintype "bidirectional"))
    )
    (net (code "89") (name "Net-(TM1637-SMD5-P$17)") (class "Default")
      (node (ref "0.1UF14") (pin "1") (pinfunction "1_1") (pintype "passive"))
      (node (ref "10K17") (pin "1") (pinfunction "1_1") (pintype "passive"))
      (node (ref "10K19") (pin "1") (pinfunction "1_1") (pintype "passive"))
      (node (ref "SV5") (pin "3") (pinfunction "3_3") (pintype "passive"))
      (node (ref "TM1637-SMD5") (pin "PIN17") (pinfunction "P$17_PIN17") (pintype "bidirectional"))
    )
    (net (code "90") (name "Net-(TM1637-SMD5-P$18)") (class "Default")
      (node (ref "0.1UF13") (pin "1") (pinfunction "1_1") (pintype "passive"))
      (node (ref "10K18") (pin "1") (pinfunction "1_1") (pintype "passive"))
      (node (ref "10K20") (pin "1") (pinfunction "1_1") (pintype "passive"))
      (node (ref "SV5") (pin "2") (pinfunction "2_2") (pintype "passive"))
      (node (ref "TM1637-SMD5") (pin "PIN18") (pinfunction "P$18_PIN18") (pintype "bidirectional"))
    )
    (net (code "91") (name "Net-(TM1637-SMD6-P$1)") (class "Default")
      (node (ref "0.1UF16") (pin "2") (pinfunction "2_2") (pintype "passive"))
      (node (ref "0.1UF17") (pin "2") (pinfunction "2_2") (pintype "passive"))
      (node (ref "0.1UF18") (pin "2") (pinfunction "2_2") (pintype "passive"))
      (node (ref "4.7UF6") (pin "2") (pinfunction "2_2") (pintype "passive"))
      (node (ref "SV6") (pin "1") (pinfunction "1_1") (pintype "passive"))
      (node (ref "TM1637-SMD6") (pin "PIN1") (pinfunction "P$1_PIN1") (pintype "bidirectional"))
    )
    (net (code "92") (name "Net-(TM1637-SMD6-P$2)") (class "Default")
      (node (ref "LED16") (pin "3") (pinfunction "3_3") (pintype "bidirectional"))
      (node (ref "LED17") (pin "3") (pinfunction "3_3") (pintype "bidirectional"))
      (node (ref "LED18") (pin "3") (pinfunction "3_3") (pintype "bidirectional"))
      (node (ref "TM1637-SMD6") (pin "PIN2") (pinfunction "P$2_PIN2") (pintype "bidirectional"))
    )
    (net (code "93") (name "Net-(TM1637-SMD6-P$3)") (class "Default")
      (node (ref "LED16") (pin "9") (pinfunction "9_9") (pintype "bidirectional"))
      (node (ref "LED17") (pin "9") (pinfunction "9_9") (pintype "bidirectional"))
      (node (ref "LED18") (pin "9") (pinfunction "9_9") (pintype "bidirectional"))
      (node (ref "TM1637-SMD6") (pin "PIN3") (pinfunction "P$3_PIN3") (pintype "bidirectional"))
    )
    (net (code "94") (name "Net-(TM1637-SMD6-P$4)") (class "Default")
      (node (ref "LED16") (pin "8") (pinfunction "8_8") (pintype "bidirectional"))
      (node (ref "LED17") (pin "8") (pinfunction "8_8") (pintype "bidirectional"))
      (node (ref "LED18") (pin "8") (pinfunction "8_8") (pintype "bidirectional"))
      (node (ref "TM1637-SMD6") (pin "PIN4") (pinfunction "P$4_PIN4") (pintype "bidirectional"))
    )
    (net (code "95") (name "Net-(TM1637-SMD6-P$5)") (class "Default")
      (node (ref "LED16") (pin "6") (pinfunction "6_6") (pintype "bidirectional"))
      (node (ref "LED17") (pin "6") (pinfunction "6_6") (pintype "bidirectional"))
      (node (ref "LED18") (pin "6") (pinfunction "6_6") (pintype "bidirectional"))
      (node (ref "TM1637-SMD6") (pin "PIN5") (pinfunction "P$5_PIN5") (pintype "bidirectional"))
    )
    (net (code "96") (name "Net-(TM1637-SMD6-P$6)") (class "Default")
      (node (ref "LED16") (pin "7") (pinfunction "7_7") (pintype "bidirectional"))
      (node (ref "LED17") (pin "7") (pinfunction "7_7") (pintype "bidirectional"))
      (node (ref "LED18") (pin "7") (pinfunction "7_7") (pintype "bidirectional"))
      (node (ref "TM1637-SMD6") (pin "PIN6") (pinfunction "P$6_PIN6") (pintype "bidirectional"))
    )
    (net (code "97") (name "Net-(TM1637-SMD6-P$7)") (class "Default")
      (node (ref "LED16") (pin "4") (pinfunction "4_4") (pintype "bidirectional"))
      (node (ref "LED17") (pin "4") (pinfunction "4_4") (pintype "bidirectional"))
      (node (ref "LED18") (pin "4") (pinfunction "4_4") (pintype "bidirectional"))
      (node (ref "TM1637-SMD6") (pin "PIN7") (pinfunction "P$7_PIN7") (pintype "bidirectional"))
    )
    (net (code "98") (name "Net-(TM1637-SMD6-P$8)") (class "Default")
      (node (ref "LED16") (pin "1") (pinfunction "1_1") (pintype "bidirectional"))
      (node (ref "LED17") (pin "1") (pinfunction "1_1") (pintype "bidirectional"))
      (node (ref "LED18") (pin "1") (pinfunction "1_1") (pintype "bidirectional"))
      (node (ref "TM1637-SMD6") (pin "PIN8") (pinfunction "P$8_PIN8") (pintype "bidirectional"))
    )
    (net (code "99") (name "Net-(TM1637-SMD6-P$9)") (class "Default")
      (node (ref "LED16") (pin "2") (pinfunction "2_2") (pintype "bidirectional"))
      (node (ref "LED17") (pin "2") (pinfunction "2_2") (pintype "bidirectional"))
      (node (ref "LED18") (pin "2") (pinfunction "2_2") (pintype "bidirectional"))
      (node (ref "TM1637-SMD6") (pin "PIN9") (pinfunction "P$9_PIN9") (pintype "bidirectional"))
    )
    (net (code "100") (name "Net-(TM1637-SMD6-P$10)") (class "Default")
      (node (ref "LED17") (pin "5") (pinfunction "5_5") (pintype "bidirectional"))
      (node (ref "TM1637-SMD6") (pin "PIN10") (pinfunction "P$10_PIN10") (pintype "bidirectional"))
    )
    (net (code "101") (name "Net-(TM1637-SMD6-P$11)") (class "Default")
      (node (ref "LED17") (pin "10") (pinfunction "10_10") (pintype "bidirectional"))
      (node (ref "TM1637-SMD6") (pin "PIN11") (pinfunction "P$11_PIN11") (pintype "bidirectional"))
    )
    (net (code "102") (name "Net-(TM1637-SMD6-P$12)") (class "Default")
      (node (ref "LED16") (pin "5") (pinfunction "5_5") (pintype "bidirectional"))
      (node (ref "TM1637-SMD6") (pin "PIN12") (pinfunction "P$12_PIN12") (pintype "bidirectional"))
    )
    (net (code "103") (name "Net-(TM1637-SMD6-P$13)") (class "Default")
      (node (ref "LED16") (pin "10") (pinfunction "10_10") (pintype "bidirectional"))
      (node (ref "TM1637-SMD6") (pin "PIN13") (pinfunction "P$13_PIN13") (pintype "bidirectional"))
    )
    (net (code "104") (name "Net-(TM1637-SMD6-P$14)") (class "Default")
      (node (ref "LED18") (pin "5") (pinfunction "5_5") (pintype "bidirectional"))
      (node (ref "TM1637-SMD6") (pin "PIN14") (pinfunction "P$14_PIN14") (pintype "bidirectional"))
    )
    (net (code "105") (name "Net-(TM1637-SMD6-P$15)") (class "Default")
      (node (ref "LED18") (pin "10") (pinfunction "10_10") (pintype "bidirectional"))
      (node (ref "TM1637-SMD6") (pin "PIN15") (pinfunction "P$15_PIN15") (pintype "bidirectional"))
    )
    (net (code "106") (name "Net-(TM1637-SMD6-P$16)") (class "Default")
      (node (ref "0.1UF18") (pin "1") (pinfunction "1_1") (pintype "passive"))
      (node (ref "10K21") (pin "2") (pinfunction "2_2") (pintype "passive"))
      (node (ref "10K22") (pin "2") (pinfunction "2_2") (pintype "passive"))
      (node (ref "10K23") (pin "2") (pinfunction "2_2") (pintype "passive"))
      (node (ref "10K24") (pin "2") (pinfunction "2_2") (pintype "passive"))
      (node (ref "4.7UF6") (pin "1") (pinfunction "1_1") (pintype "passive"))
      (node (ref "SV6") (pin "4") (pinfunction "4_4") (pintype "passive"))
      (node (ref "TM1637-SMD6") (pin "PIN16") (pinfunction "P$16_PIN16") (pintype "bidirectional"))
    )
    (net (code "107") (name "Net-(TM1637-SMD6-P$17)") (class "Default")
      (node (ref "0.1UF17") (pin "1") (pinfunction "1_1") (pintype "passive"))
      (node (ref "10K21") (pin "1") (pinfunction "1_1") (pintype "passive"))
      (node (ref "10K23") (pin "1") (pinfunction "1_1") (pintype "passive"))
      (node (ref "SV6") (pin "3") (pinfunction "3_3") (pintype "passive"))
      (node (ref "TM1637-SMD6") (pin "PIN17") (pinfunction "P$17_PIN17") (pintype "bidirectional"))
    )
    (net (code "108") (name "Net-(TM1637-SMD6-P$18)") (class "Default")
      (node (ref "0.1UF16") (pin "1") (pinfunction "1_1") (pintype "passive"))
      (node (ref "10K22") (pin "1") (pinfunction "1_1") (pintype "passive"))
      (node (ref "10K24") (pin "1") (pinfunction "1_1") (pintype "passive"))
      (node (ref "SV6") (pin "2") (pinfunction "2_2") (pintype "passive"))
      (node (ref "TM1637-SMD6") (pin "PIN18") (pinfunction "P$18_PIN18") (pintype "bidirectional"))
    )
    (net (code "109") (name "unconnected-(TM1637-SMD1-P$19-PadPIN19)") (class "Default")
      (node (ref "TM1637-SMD1") (pin "PIN19") (pinfunction "P$19_PIN19") (pintype "bidirectional"))
    )
    (net (code "110") (name "unconnected-(TM1637-SMD1-P$20-PadPIN20)") (class "Default")
      (node (ref "TM1637-SMD1") (pin "PIN20") (pinfunction "P$20_PIN20") (pintype "bidirectional"))
    )
    (net (code "111") (name "unconnected-(TM1637-SMD2-P$19-PadPIN19)") (class "Default")
      (node (ref "TM1637-SMD2") (pin "PIN19") (pinfunction "P$19_PIN19") (pintype "bidirectional"))
    )
    (net (code "112") (name "unconnected-(TM1637-SMD2-P$20-PadPIN20)") (class "Default")
      (node (ref "TM1637-SMD2") (pin "PIN20") (pinfunction "P$20_PIN20") (pintype "bidirectional"))
    )
    (net (code "113") (name "unconnected-(TM1637-SMD3-P$19-PadPIN19)") (class "Default")
      (node (ref "TM1637-SMD3") (pin "PIN19") (pinfunction "P$19_PIN19") (pintype "bidirectional"))
    )
    (net (code "114") (name "unconnected-(TM1637-SMD3-P$20-PadPIN20)") (class "Default")
      (node (ref "TM1637-SMD3") (pin "PIN20") (pinfunction "P$20_PIN20") (pintype "bidirectional"))
    )
    (net (code "115") (name "unconnected-(TM1637-SMD4-P$19-PadPIN19)") (class "Default")
      (node (ref "TM1637-SMD4") (pin "PIN19") (pinfunction "P$19_PIN19") (pintype "bidirectional"))
    )
    (net (code "116") (name "unconnected-(TM1637-SMD4-P$20-PadPIN20)") (class "Default")
      (node (ref "TM1637-SMD4") (pin "PIN20") (pinfunction "P$20_PIN20") (pintype "bidirectional"))
    )
    (net (code "117") (name "unconnected-(TM1637-SMD5-P$19-PadPIN19)") (class "Default")
      (node (ref "TM1637-SMD5") (pin "PIN19") (pinfunction "P$19_PIN19") (pintype "bidirectional"))
    )
    (net (code "118") (name "unconnected-(TM1637-SMD5-P$20-PadPIN20)") (class "Default")
      (node (ref "TM1637-SMD5") (pin "PIN20") (pinfunction "P$20_PIN20") (pintype "bidirectional"))
    )
    (net (code "119") (name "unconnected-(TM1637-SMD6-P$19-PadPIN19)") (class "Default")
      (node (ref "TM1637-SMD6") (pin "PIN19") (pinfunction "P$19_PIN19") (pintype "bidirectional"))
    )
    (net (code "120") (name "unconnected-(TM1637-SMD6-P$20-PadPIN20)") (class "Default")
      (node (ref "TM1637-SMD6") (pin "PIN20") (pinfunction "P$20_PIN20") (pintype "bidirectional"))
    )
  )
)
